# Clocks_gen.net
KiCad netlist of a schematic drawn in Altium Designer
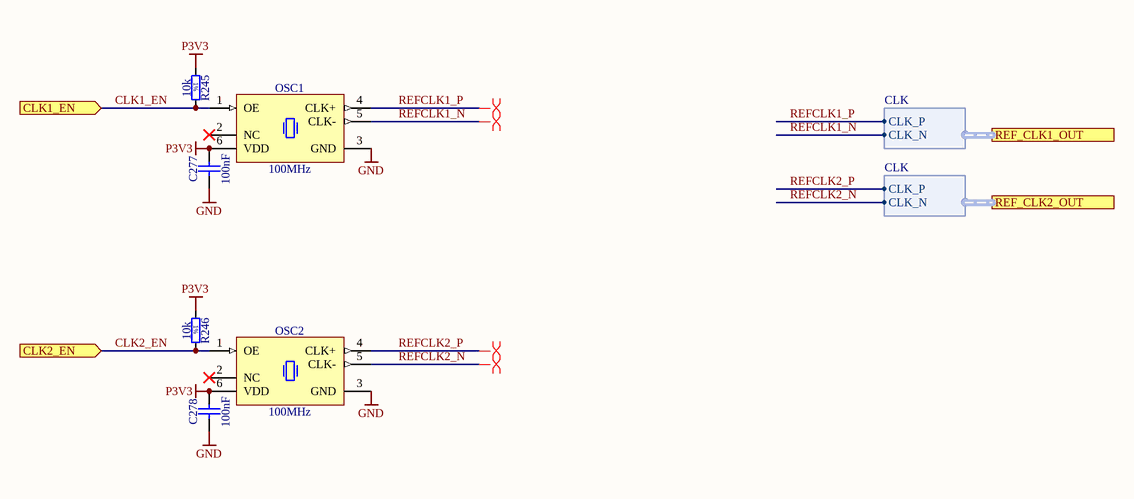
[diagram p0: Clocks_gen.SchDoc]

(export (version "E")
  (design (tool "Eeschema 10.0.6"))
  (components
    (comp (ref "C277")
      (value "100nF")
      (footprint "CAPC1005X55N")
      (description "Non-polarised capacitor")
      (fields
        (field (name "PART NUMBER") "CC0402_100NF_25V_10%_X7R_YUDEN_TMK105B7104KVHF")
        (field (name "VOLTAGE") "25V")
        (field (name "AUTHOR") "CERN DEM JLC")
      )
      (libsource (lib "Capacitors") (part "Capacitor - non polarized"))
    )
    (comp (ref "C278")
      (value "100nF")
      (footprint "CAPC1005X55N")
      (description "Non-polarised capacitor")
      (fields
        (field (name "PART NUMBER") "CC0402_100NF_25V_10%_X7R_YUDEN_TMK105B7104KVHF")
        (field (name "VOLTAGE") "25V")
        (field (name "AUTHOR") "CERN DEM JLC")
      )
      (libsource (lib "Capacitors") (part "Capacitor - non polarized"))
    )
    (comp (ref "OSC1")
      (value "100MHz")
      (footprint "OSC_SILICON-LAB_SI531")
      (description "10-1400MHz, Crystal Oscillator (XO), Si531 Series")
      (fields
        (field (name "PART NUMBER") "OSC_100MHZ_SILICON-LAB_531BC100M000DG")
        (field (name "MANUFACTURER") "SILICON LABS")
        (field (name "AUTHOR") "CERN DEM MR")
      )
      (libsource (lib "ICs And Semiconductors") (part "Oscillator SILICON-LAB_Si531"))
    )
    (comp (ref "OSC2")
      (value "100MHz")
      (footprint "OSC_SILICON-LAB_SI531")
      (description "10-1400MHz, Crystal Oscillator (XO), Si531 Series")
      (fields
        (field (name "PART NUMBER") "OSC_100MHZ_SILICON-LAB_531BC100M000DG")
        (field (name "MANUFACTURER") "SILICON LABS")
        (field (name "AUTHOR") "CERN DEM MR")
      )
      (libsource (lib "ICs And Semiconductors") (part "Oscillator SILICON-LAB_Si531"))
    )
    (comp (ref "R245")
      (value "10k")
      (footprint "RESC1005X40N")
      (description "Resistor - 1%")
      (fields
        (field (name "PART NUMBER") "R0402_10K_1%_0.0625W_100PPM")
        (field (name "POWER") "0.0625W")
        (field (name "AUTHOR") "CERN DEM JLC")
      )
      (libsource (lib "Resistors") (part "Resistor - 1%"))
    )
    (comp (ref "R246")
      (value "10k")
      (footprint "RESC1005X40N")
      (description "Resistor - 1%")
      (fields
        (field (name "PART NUMBER") "R0402_10K_1%_0.0625W_100PPM")
        (field (name "POWER") "0.0625W")
        (field (name "AUTHOR") "CERN DEM JLC")
      )
      (libsource (lib "Resistors") (part "Resistor - 1%"))
    )
  )
  (nets
    (net (code "2") (name "/CLK1_EN") (class "Default")
      (node (ref "OSC1") (pin "1") (pinfunction "OE_1") (pintype "input"))
      (node (ref "R245") (pin "2") (pinfunction "2_2") (pintype "passive"))
    )
    (net (code "3") (name "/CLK2_EN") (class "Default")
      (node (ref "OSC2") (pin "1") (pinfunction "OE_1") (pintype "input"))
      (node (ref "R246") (pin "2") (pinfunction "2_2") (pintype "passive"))
    )
    (net (code "4") (name "/REFCLK1_N") (class "Default")
      (node (ref "OSC1") (pin "5") (pinfunction "CLK-_5") (pintype "output"))
    )
    (net (code "5") (name "/REFCLK1_P") (class "Default")
      (node (ref "OSC1") (pin "4") (pinfunction "CLK+_4") (pintype "output"))
    )
    (net (code "6") (name "/REFCLK2_N") (class "Default")
      (node (ref "OSC2") (pin "5") (pinfunction "CLK-_5") (pintype "output"))
    )
    (net (code "7") (name "/REFCLK2_P") (class "Default")
      (node (ref "OSC2") (pin "4") (pinfunction "CLK+_4") (pintype "output"))
    )
    (net (code "9") (name "GND") (class "Default")
      (node (ref "C277") (pin "1") (pinfunction "1_1") (pintype "passive"))
      (node (ref "C278") (pin "1") (pinfunction "1_1") (pintype "passive"))
      (node (ref "OSC1") (pin "3") (pinfunction "GND_3") (pintype "power_in"))
      (node (ref "OSC2") (pin "3") (pinfunction "GND_3") (pintype "power_in"))
    )
    (net (code "10") (name "P3V3") (class "Default")
      (node (ref "C277") (pin "2") (pinfunction "2_2") (pintype "passive"))
      (node (ref "C278") (pin "2") (pinfunction "2_2") (pintype "passive"))
      (node (ref "OSC1") (pin "6") (pinfunction "VDD_6") (pintype "power_in"))
      (node (ref "OSC2") (pin "6") (pinfunction "VDD_6") (pintype "power_in"))
      (node (ref "R245") (pin "1") (pinfunction "1_1") (pintype "passive"))
      (node (ref "R246") (pin "1") (pinfunction "1_1") (pintype "passive"))
    )
    (net (code "11") (name "unconnected-(OSC1-NC-Pad2)") (class "Default")
      (node (ref "OSC1") (pin "2") (pinfunction "NC_2") (pintype "passive+no_connect"))
    )
    (net (code "12") (name "unconnected-(OSC2-NC-Pad2)") (class "Default")
      (node (ref "OSC2") (pin "2") (pinfunction "NC_2") (pintype "passive+no_connect"))
    )
  )
)
